# A214A.net
KiCad netlist of a schematic drawn in EAGLE
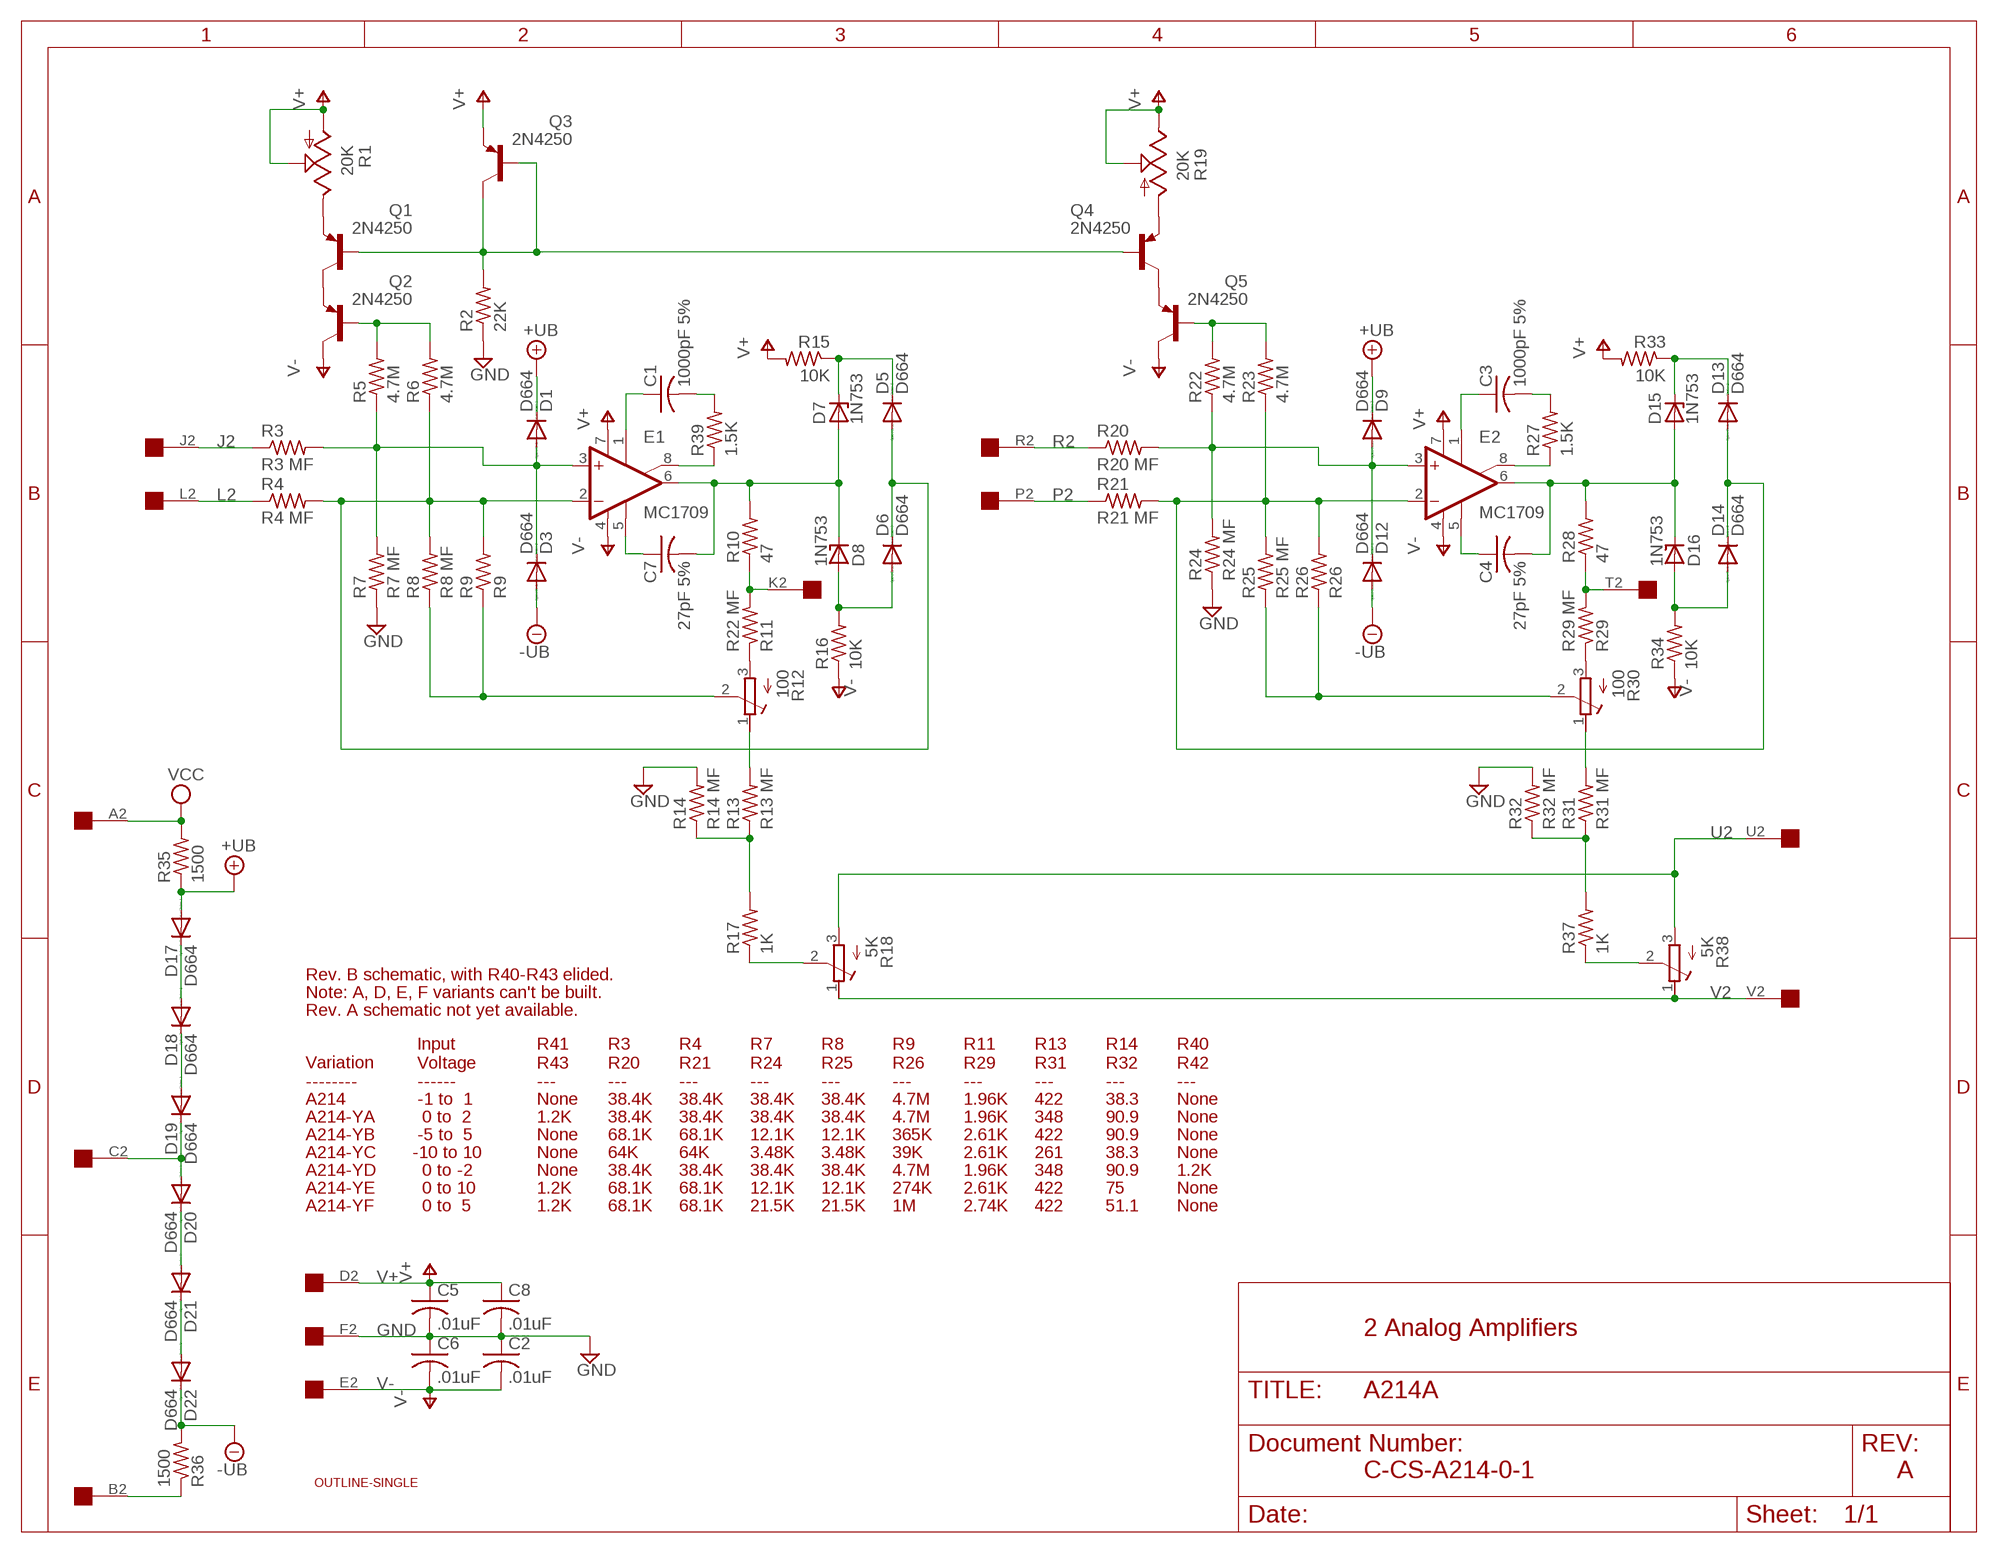
[diagram p0: schematic, sheet 1]

(export (version "E")
  (design (tool "Eeschema 10.0.6"))
  (components
    (comp (ref "C1")
      (value "1000pF 5%")
      (footprint "eagle-import:C050-030X075")
      (libsource (lib "eagle-import") (part "C-US050-030X075"))
    )
    (comp (ref "C2")
      (value ".01uF")
      (footprint "eagle-import:C063-025X075")
      (libsource (lib "eagle-import") (part "C-US"))
    )
    (comp (ref "C3")
      (value "1000pF 5%")
      (footprint "eagle-import:C050-030X075")
      (libsource (lib "eagle-import") (part "C-US050-030X075"))
    )
    (comp (ref "C4")
      (value "27pF 5%")
      (footprint "eagle-import:C063-025X075")
      (libsource (lib "eagle-import") (part "C-US"))
    )
    (comp (ref "C5")
      (value ".01uF")
      (footprint "eagle-import:C063-025X075")
      (libsource (lib "eagle-import") (part "C-US"))
    )
    (comp (ref "C6")
      (value ".01uF")
      (footprint "eagle-import:C063-025X075")
      (libsource (lib "eagle-import") (part "C-US"))
    )
    (comp (ref "C7")
      (value "27pF 5%")
      (footprint "eagle-import:C063-025X075")
      (libsource (lib "eagle-import") (part "C-US"))
    )
    (comp (ref "C8")
      (value ".01uF")
      (footprint "eagle-import:C063-025X075")
      (libsource (lib "eagle-import") (part "C-US"))
    )
    (comp (ref "D1")
      (value "D664")
      (footprint "eagle-import:DO35-10")
      (libsource (lib "eagle-import") (part "DIODE-DO35-10"))
    )
    (comp (ref "D3")
      (value "D664")
      (footprint "eagle-import:DO35-10")
      (libsource (lib "eagle-import") (part "DIODE-DO35-10"))
    )
    (comp (ref "D5")
      (value "D664")
      (footprint "eagle-import:DO35-10")
      (libsource (lib "eagle-import") (part "DIODE-DO35-10"))
    )
    (comp (ref "D6")
      (value "D664")
      (footprint "eagle-import:DO35-10")
      (libsource (lib "eagle-import") (part "DIODE-DO35-10"))
    )
    (comp (ref "D7")
      (value "1N753")
      (footprint "eagle-import:DO41Z10")
      (libsource (lib "eagle-import") (part "ZENER-DIODEDO41Z10"))
    )
    (comp (ref "D8")
      (value "1N753")
      (footprint "eagle-import:DO41Z10")
      (libsource (lib "eagle-import") (part "ZENER-DIODEDO41Z10"))
    )
    (comp (ref "D9")
      (value "D664")
      (footprint "eagle-import:DO35-10")
      (libsource (lib "eagle-import") (part "DIODE-DO35-10"))
    )
    (comp (ref "D12")
      (value "D664")
      (footprint "eagle-import:DO35-10")
      (libsource (lib "eagle-import") (part "DIODE-DO35-10"))
    )
    (comp (ref "D13")
      (value "D664")
      (footprint "eagle-import:DO35-10")
      (libsource (lib "eagle-import") (part "DIODE-DO35-10"))
    )
    (comp (ref "D14")
      (value "D664")
      (footprint "eagle-import:DO35-10")
      (libsource (lib "eagle-import") (part "DIODE-DO35-10"))
    )
    (comp (ref "D15")
      (value "1N753")
      (footprint "eagle-import:DO41Z10")
      (libsource (lib "eagle-import") (part "ZENER-DIODEDO41Z10"))
    )
    (comp (ref "D16")
      (value "1N753")
      (footprint "eagle-import:DO41Z10")
      (libsource (lib "eagle-import") (part "ZENER-DIODEDO41Z10"))
    )
    (comp (ref "D17")
      (value "D664")
      (footprint "eagle-import:DO35-10")
      (libsource (lib "eagle-import") (part "DIODE-DO35-10"))
    )
    (comp (ref "D18")
      (value "D664")
      (footprint "eagle-import:DO35-10")
      (libsource (lib "eagle-import") (part "DIODE-DO35-10"))
    )
    (comp (ref "D19")
      (value "D664")
      (footprint "eagle-import:DO35-10")
      (libsource (lib "eagle-import") (part "DIODE-DO35-10"))
    )
    (comp (ref "D20")
      (value "D664")
      (footprint "eagle-import:DO35-10")
      (libsource (lib "eagle-import") (part "DIODE-DO35-10"))
    )
    (comp (ref "D21")
      (value "D664")
      (footprint "eagle-import:DO35-10")
      (libsource (lib "eagle-import") (part "DIODE-DO35-10"))
    )
    (comp (ref "D22")
      (value "D664")
      (footprint "eagle-import:DO35-10")
      (libsource (lib "eagle-import") (part "DIODE-DO35-10"))
    )
    (comp (ref "E1")
      (value "MC1709")
      (footprint "eagle-import:H08C")
      (libsource (lib "eagle-import") (part "MC1709"))
    )
    (comp (ref "E2")
      (value "MC1709")
      (footprint "eagle-import:H08C")
      (libsource (lib "eagle-import") (part "MC1709"))
    )
    (comp (ref "Q1")
      (value "2N4250")
      (footprint "eagle-import:TO5")
      (libsource (lib "eagle-import") (part "-PNP-TO5"))
    )
    (comp (ref "Q2")
      (value "2N4250")
      (footprint "eagle-import:TO5")
      (libsource (lib "eagle-import") (part "-PNP-TO5"))
    )
    (comp (ref "Q3")
      (value "2N4250")
      (footprint "eagle-import:TO5")
      (libsource (lib "eagle-import") (part "-PNP-TO5"))
    )
    (comp (ref "Q4")
      (value "2N4250")
      (footprint "eagle-import:TO5")
      (libsource (lib "eagle-import") (part "-PNP-TO5"))
    )
    (comp (ref "Q5")
      (value "2N4250")
      (footprint "eagle-import:TO5")
      (libsource (lib "eagle-import") (part "-PNP-TO5"))
    )
    (comp (ref "R1")
      (value "20K")
      (footprint "eagle-import:B25P")
      (libsource (lib "eagle-import") (part "TRIM_US-B25P"))
    )
    (comp (ref "R2")
      (value "22K")
      (footprint "eagle-import:0207_10")
      (libsource (lib "eagle-import") (part "R-US_0207/10"))
    )
    (comp (ref "R3")
      (value "R3 MF")
      (footprint "eagle-import:0207_15")
      (libsource (lib "eagle-import") (part "R-US_0207/15"))
    )
    (comp (ref "R4")
      (value "R4 MF")
      (footprint "eagle-import:0207_15")
      (libsource (lib "eagle-import") (part "R-US_0207/15"))
    )
    (comp (ref "R5")
      (value "4.7M")
      (footprint "eagle-import:0207_10")
      (libsource (lib "eagle-import") (part "R-US_0207/10"))
    )
    (comp (ref "R6")
      (value "4.7M")
      (footprint "eagle-import:0207_10")
      (libsource (lib "eagle-import") (part "R-US_0207/10"))
    )
    (comp (ref "R7")
      (value "R7 MF")
      (footprint "eagle-import:0207_15")
      (libsource (lib "eagle-import") (part "R-US_0207/15"))
    )
    (comp (ref "R8")
      (value "R8 MF")
      (footprint "eagle-import:0207_15")
      (libsource (lib "eagle-import") (part "R-US_0207/15"))
    )
    (comp (ref "R9")
      (value "R9")
      (footprint "eagle-import:0207_10")
      (libsource (lib "eagle-import") (part "R-US_0207/10"))
    )
    (comp (ref "R10")
      (value "47")
      (footprint "eagle-import:0207_10")
      (libsource (lib "eagle-import") (part "R-US_0207/10"))
    )
    (comp (ref "R11")
      (value "R22 MF")
      (footprint "eagle-import:0207_15")
      (libsource (lib "eagle-import") (part "R-US_0207/15"))
    )
    (comp (ref "R12")
      (value "100")
      (footprint "eagle-import:3006Y")
      (libsource (lib "eagle-import") (part "275P"))
    )
    (comp (ref "R13")
      (value "R13 MF")
      (footprint "eagle-import:0207_15")
      (libsource (lib "eagle-import") (part "R-US_0207/15"))
    )
    (comp (ref "R14")
      (value "R14 MF")
      (footprint "eagle-import:0207_15")
      (libsource (lib "eagle-import") (part "R-US_0207/15"))
    )
    (comp (ref "R15")
      (value "10K")
      (footprint "eagle-import:0207_10")
      (libsource (lib "eagle-import") (part "R-US_0207/10"))
    )
    (comp (ref "R16")
      (value "10K")
      (footprint "eagle-import:0207_10")
      (libsource (lib "eagle-import") (part "R-US_0207/10"))
    )
    (comp (ref "R17")
      (value "1K")
      (footprint "eagle-import:0207_10")
      (libsource (lib "eagle-import") (part "R-US_0207/10"))
    )
    (comp (ref "R18")
      (value "5K")
      (footprint "eagle-import:3006Y")
      (libsource (lib "eagle-import") (part "275P"))
    )
    (comp (ref "R19")
      (value "20K")
      (footprint "eagle-import:B25P")
      (libsource (lib "eagle-import") (part "TRIM_US-B25P"))
    )
    (comp (ref "R20")
      (value "R20 MF")
      (footprint "eagle-import:0207_15")
      (libsource (lib "eagle-import") (part "R-US_0207/15"))
    )
    (comp (ref "R21")
      (value "R21 MF")
      (footprint "eagle-import:0207_15")
      (libsource (lib "eagle-import") (part "R-US_0207/15"))
    )
    (comp (ref "R22")
      (value "4.7M")
      (footprint "eagle-import:0207_10")
      (libsource (lib "eagle-import") (part "R-US_0207/10"))
    )
    (comp (ref "R23")
      (value "4.7M")
      (footprint "eagle-import:0207_10")
      (libsource (lib "eagle-import") (part "R-US_0207/10"))
    )
    (comp (ref "R24")
      (value "R24 MF")
      (footprint "eagle-import:0207_15")
      (libsource (lib "eagle-import") (part "R-US_0207/15"))
    )
    (comp (ref "R25")
      (value "R25 MF")
      (footprint "eagle-import:0207_15")
      (libsource (lib "eagle-import") (part "R-US_0207/15"))
    )
    (comp (ref "R26")
      (value "R26")
      (footprint "eagle-import:0207_10")
      (libsource (lib "eagle-import") (part "R-US_0207/10"))
    )
    (comp (ref "R27")
      (value "1.5K")
      (footprint "eagle-import:0207_10")
      (libsource (lib "eagle-import") (part "R-US_0207/10"))
    )
    (comp (ref "R28")
      (value "47")
      (footprint "eagle-import:0207_10")
      (libsource (lib "eagle-import") (part "R-US_0207/10"))
    )
    (comp (ref "R29")
      (value "R29 MF")
      (footprint "eagle-import:0207_15")
      (libsource (lib "eagle-import") (part "R-US_0207/15"))
    )
    (comp (ref "R30")
      (value "100")
      (footprint "eagle-import:3006Y")
      (libsource (lib "eagle-import") (part "275P"))
    )
    (comp (ref "R31")
      (value "R31 MF")
      (footprint "eagle-import:0207_15")
      (libsource (lib "eagle-import") (part "R-US_0207/15"))
    )
    (comp (ref "R32")
      (value "R32 MF")
      (footprint "eagle-import:0207_15")
      (libsource (lib "eagle-import") (part "R-US_0207/15"))
    )
    (comp (ref "R33")
      (value "10K")
      (footprint "eagle-import:0207_10")
      (libsource (lib "eagle-import") (part "R-US_0207/10"))
    )
    (comp (ref "R34")
      (value "10K")
      (footprint "eagle-import:0207_10")
      (libsource (lib "eagle-import") (part "R-US_0207/10"))
    )
    (comp (ref "R35")
      (value "1500")
      (footprint "eagle-import:0207_10")
      (libsource (lib "eagle-import") (part "R-US_0207/10"))
    )
    (comp (ref "R36")
      (value "1500")
      (footprint "eagle-import:0207_10")
      (libsource (lib "eagle-import") (part "R-US_0207/10"))
    )
    (comp (ref "R37")
      (value "1K")
      (footprint "eagle-import:0207_10")
      (libsource (lib "eagle-import") (part "R-US_0207/10"))
    )
    (comp (ref "R38")
      (value "5K")
      (footprint "eagle-import:3006Y")
      (libsource (lib "eagle-import") (part "275P"))
    )
    (comp (ref "R39")
      (value "1.5K")
      (footprint "eagle-import:0207_10")
      (libsource (lib "eagle-import") (part "R-US_0207/10"))
    )
    (comp (ref "U$1")
      (value "OUTLINE-SINGLE")
      (footprint "eagle-import:SINGLE")
      (libsource (lib "eagle-import") (part "OUTLINE-SINGLE"))
    )
    (comp (ref "U$2")
      (value "SINGLE")
      (footprint "eagle-import:EDGE-CON2")
      (libsource (lib "eagle-import") (part "SINGLE"))
    )
  )
  (nets
    (net (code "1") (name "+UB") (class "Default")
      (node (ref "D1") (pin "C") (pinfunction "C_C") (pintype "passive"))
      (node (ref "D17") (pin "A") (pinfunction "A_A") (pintype "passive"))
      (node (ref "D9") (pin "C") (pinfunction "C_C") (pintype "passive"))
      (node (ref "R35") (pin "1") (pinfunction "1_1") (pintype "passive"))
    )
    (net (code "2") (name "-UB") (class "Default")
      (node (ref "D12") (pin "A") (pinfunction "A_A") (pintype "passive"))
      (node (ref "D22") (pin "C") (pinfunction "C_C") (pintype "passive"))
      (node (ref "D3") (pin "A") (pinfunction "A_A") (pintype "passive"))
      (node (ref "R36") (pin "2") (pinfunction "2_2") (pintype "passive"))
    )
    (net (code "3") (name "/J2") (class "Default")
      (node (ref "R3") (pin "1") (pinfunction "1_1") (pintype "passive"))
      (node (ref "U$2") (pin "J2") (pinfunction "1_J2") (pintype "bidirectional"))
    )
    (net (code "4") (name "/L2") (class "Default")
      (node (ref "R4") (pin "1") (pinfunction "1_1") (pintype "passive"))
      (node (ref "U$2") (pin "L2") (pinfunction "1_L2") (pintype "bidirectional"))
    )
    (net (code "5") (name "/P2") (class "Default")
      (node (ref "R21") (pin "1") (pinfunction "1_1") (pintype "passive"))
      (node (ref "U$2") (pin "P2") (pinfunction "1_P2") (pintype "bidirectional"))
    )
    (net (code "6") (name "/R2") (class "Default")
      (node (ref "R20") (pin "1") (pinfunction "1_1") (pintype "passive"))
      (node (ref "U$2") (pin "R2") (pinfunction "1_R2") (pintype "bidirectional"))
    )
    (net (code "7") (name "/U2") (class "Default")
      (node (ref "R18") (pin "3") (pinfunction "E_3") (pintype "passive"))
      (node (ref "R38") (pin "3") (pinfunction "E_3") (pintype "passive"))
      (node (ref "U$2") (pin "U2") (pinfunction "1_U2") (pintype "bidirectional"))
    )
    (net (code "8") (name "/V2") (class "Default")
      (node (ref "R18") (pin "1") (pinfunction "A_1") (pintype "passive"))
      (node (ref "R38") (pin "1") (pinfunction "A_1") (pintype "passive"))
      (node (ref "U$2") (pin "V2") (pinfunction "1_V2") (pintype "bidirectional"))
    )
    (net (code "9") (name "GND") (class "Default")
      (node (ref "C2") (pin "1") (pinfunction "1_1") (pintype "passive"))
      (node (ref "C5") (pin "2") (pinfunction "2_2") (pintype "passive"))
      (node (ref "C6") (pin "1") (pinfunction "1_1") (pintype "passive"))
      (node (ref "C8") (pin "2") (pinfunction "2_2") (pintype "passive"))
      (node (ref "R14") (pin "2") (pinfunction "2_2") (pintype "passive"))
      (node (ref "R2") (pin "1") (pinfunction "1_1") (pintype "passive"))
      (node (ref "R24") (pin "1") (pinfunction "1_1") (pintype "passive"))
      (node (ref "R32") (pin "2") (pinfunction "2_2") (pintype "passive"))
      (node (ref "R7") (pin "1") (pinfunction "1_1") (pintype "passive"))
      (node (ref "U$2") (pin "F2") (pinfunction "1_F2") (pintype "bidirectional"))
    )
    (net (code "10") (name "Net-(C1-Pad2)") (class "Default")
      (node (ref "C1") (pin "2") (pinfunction "2_2") (pintype "passive"))
      (node (ref "R39") (pin "2") (pinfunction "2_2") (pintype "passive"))
    )
    (net (code "11") (name "Net-(C3-Pad2)") (class "Default")
      (node (ref "C3") (pin "2") (pinfunction "2_2") (pintype "passive"))
      (node (ref "R27") (pin "2") (pinfunction "2_2") (pintype "passive"))
    )
    (net (code "12") (name "Net-(D5-PadC)") (class "Default")
      (node (ref "D5") (pin "C") (pinfunction "C_C") (pintype "passive"))
      (node (ref "D7") (pin "C") (pinfunction "C_C") (pintype "passive"))
      (node (ref "R15") (pin "1") (pinfunction "1_1") (pintype "passive"))
    )
    (net (code "13") (name "Net-(D6-PadA)") (class "Default")
      (node (ref "D6") (pin "A") (pinfunction "A_A") (pintype "passive"))
      (node (ref "D8") (pin "A") (pinfunction "A_A") (pintype "passive"))
      (node (ref "R16") (pin "2") (pinfunction "2_2") (pintype "passive"))
    )
    (net (code "14") (name "Net-(D13-PadC)") (class "Default")
      (node (ref "D13") (pin "C") (pinfunction "C_C") (pintype "passive"))
      (node (ref "D15") (pin "C") (pinfunction "C_C") (pintype "passive"))
      (node (ref "R33") (pin "1") (pinfunction "1_1") (pintype "passive"))
    )
    (net (code "15") (name "Net-(D14-PadA)") (class "Default")
      (node (ref "D14") (pin "A") (pinfunction "A_A") (pintype "passive"))
      (node (ref "D16") (pin "A") (pinfunction "A_A") (pintype "passive"))
      (node (ref "R34") (pin "2") (pinfunction "2_2") (pintype "passive"))
    )
    (net (code "16") (name "Net-(D17-PadC)") (class "Default")
      (node (ref "D17") (pin "C") (pinfunction "C_C") (pintype "passive"))
      (node (ref "D18") (pin "A") (pinfunction "A_A") (pintype "passive"))
    )
    (net (code "17") (name "Net-(D18-PadC)") (class "Default")
      (node (ref "D18") (pin "C") (pinfunction "C_C") (pintype "passive"))
      (node (ref "D19") (pin "A") (pinfunction "A_A") (pintype "passive"))
    )
    (net (code "18") (name "Net-(D20-PadC)") (class "Default")
      (node (ref "D20") (pin "C") (pinfunction "C_C") (pintype "passive"))
      (node (ref "D21") (pin "A") (pinfunction "A_A") (pintype "passive"))
    )
    (net (code "19") (name "Net-(D21-PadC)") (class "Default")
      (node (ref "D21") (pin "C") (pinfunction "C_C") (pintype "passive"))
      (node (ref "D22") (pin "A") (pinfunction "A_A") (pintype "passive"))
    )
    (net (code "20") (name "Net-(E1-+IN)") (class "Default")
      (node (ref "D1") (pin "A") (pinfunction "A_A") (pintype "passive"))
      (node (ref "D3") (pin "C") (pinfunction "C_C") (pintype "passive"))
      (node (ref "E1") (pin "3") (pinfunction "+IN_3") (pintype "input"))
      (node (ref "R3") (pin "2") (pinfunction "2_2") (pintype "passive"))
      (node (ref "R5") (pin "1") (pinfunction "1_1") (pintype "passive"))
      (node (ref "R7") (pin "2") (pinfunction "2_2") (pintype "passive"))
    )
    (net (code "21") (name "Net-(E1--IN)") (class "Default")
      (node (ref "D5") (pin "A") (pinfunction "A_A") (pintype "passive"))
      (node (ref "D6") (pin "C") (pinfunction "C_C") (pintype "passive"))
      (node (ref "E1") (pin "2") (pinfunction "-IN_2") (pintype "input"))
      (node (ref "R4") (pin "2") (pinfunction "2_2") (pintype "passive"))
      (node (ref "R6") (pin "1") (pinfunction "1_1") (pintype "passive"))
      (node (ref "R8") (pin "2") (pinfunction "2_2") (pintype "passive"))
      (node (ref "R9") (pin "2") (pinfunction "2_2") (pintype "passive"))
    )
    (net (code "22") (name "Net-(E1-ON1)") (class "Default")
      (node (ref "C1") (pin "1") (pinfunction "1_1") (pintype "passive"))
      (node (ref "E1") (pin "1") (pinfunction "ON1_1") (pintype "passive"))
    )
    (net (code "23") (name "Net-(E1-ON2)") (class "Default")
      (node (ref "E1") (pin "8") (pinfunction "ON2_8") (pintype "passive"))
      (node (ref "R39") (pin "1") (pinfunction "1_1") (pintype "passive"))
    )
    (net (code "24") (name "Net-(E1-OPT)") (class "Default")
      (node (ref "C7") (pin "1") (pinfunction "1_1") (pintype "passive"))
      (node (ref "E1") (pin "5") (pinfunction "OPT_5") (pintype "passive"))
    )
    (net (code "25") (name "Net-(E1-OUT)") (class "Default")
      (node (ref "C7") (pin "2") (pinfunction "2_2") (pintype "passive"))
      (node (ref "D7") (pin "A") (pinfunction "A_A") (pintype "passive"))
      (node (ref "D8") (pin "C") (pinfunction "C_C") (pintype "passive"))
      (node (ref "E1") (pin "6") (pinfunction "OUT_6") (pintype "output"))
      (node (ref "R10") (pin "2") (pinfunction "2_2") (pintype "passive"))
    )
    (net (code "26") (name "Net-(E2-+IN)") (class "Default")
      (node (ref "D12") (pin "C") (pinfunction "C_C") (pintype "passive"))
      (node (ref "D9") (pin "A") (pinfunction "A_A") (pintype "passive"))
      (node (ref "E2") (pin "3") (pinfunction "+IN_3") (pintype "input"))
      (node (ref "R20") (pin "2") (pinfunction "2_2") (pintype "passive"))
      (node (ref "R22") (pin "1") (pinfunction "1_1") (pintype "passive"))
      (node (ref "R24") (pin "2") (pinfunction "2_2") (pintype "passive"))
    )
    (net (code "27") (name "Net-(E2--IN)") (class "Default")
      (node (ref "D13") (pin "A") (pinfunction "A_A") (pintype "passive"))
      (node (ref "D14") (pin "C") (pinfunction "C_C") (pintype "passive"))
      (node (ref "E2") (pin "2") (pinfunction "-IN_2") (pintype "input"))
      (node (ref "R21") (pin "2") (pinfunction "2_2") (pintype "passive"))
      (node (ref "R23") (pin "1") (pinfunction "1_1") (pintype "passive"))
      (node (ref "R25") (pin "2") (pinfunction "2_2") (pintype "passive"))
      (node (ref "R26") (pin "2") (pinfunction "2_2") (pintype "passive"))
    )
    (net (code "28") (name "Net-(E2-ON1)") (class "Default")
      (node (ref "C3") (pin "1") (pinfunction "1_1") (pintype "passive"))
      (node (ref "E2") (pin "1") (pinfunction "ON1_1") (pintype "passive"))
    )
    (net (code "29") (name "Net-(E2-ON2)") (class "Default")
      (node (ref "E2") (pin "8") (pinfunction "ON2_8") (pintype "passive"))
      (node (ref "R27") (pin "1") (pinfunction "1_1") (pintype "passive"))
    )
    (net (code "30") (name "Net-(E2-OPT)") (class "Default")
      (node (ref "C4") (pin "1") (pinfunction "1_1") (pintype "passive"))
      (node (ref "E2") (pin "5") (pinfunction "OPT_5") (pintype "passive"))
    )
    (net (code "31") (name "Net-(E2-OUT)") (class "Default")
      (node (ref "C4") (pin "2") (pinfunction "2_2") (pintype "passive"))
      (node (ref "D15") (pin "A") (pinfunction "A_A") (pintype "passive"))
      (node (ref "D16") (pin "C") (pinfunction "C_C") (pintype "passive"))
      (node (ref "E2") (pin "6") (pinfunction "OUT_6") (pintype "output"))
      (node (ref "R28") (pin "2") (pinfunction "2_2") (pintype "passive"))
    )
    (net (code "32") (name "Net-(Q1-B)") (class "Default")
      (node (ref "Q1") (pin "2") (pinfunction "B_2") (pintype "passive"))
      (node (ref "Q3") (pin "2") (pinfunction "B_2") (pintype "passive"))
      (node (ref "Q3") (pin "3") (pinfunction "C_3") (pintype "passive"))
      (node (ref "Q4") (pin "2") (pinfunction "B_2") (pintype "passive"))
      (node (ref "R2") (pin "2") (pinfunction "2_2") (pintype "passive"))
    )
    (net (code "33") (name "Net-(Q1-C)") (class "Default")
      (node (ref "Q1") (pin "3") (pinfunction "C_3") (pintype "passive"))
      (node (ref "Q2") (pin "1") (pinfunction "E_1") (pintype "passive"))
    )
    (net (code "34") (name "Net-(Q1-E)") (class "Default")
      (node (ref "Q1") (pin "1") (pinfunction "E_1") (pintype "passive"))
      (node (ref "R1") (pin "E") (pinfunction "E_E") (pintype "passive"))
    )
    (net (code "35") (name "Net-(Q2-B)") (class "Default")
      (node (ref "Q2") (pin "2") (pinfunction "B_2") (pintype "passive"))
      (node (ref "R5") (pin "2") (pinfunction "2_2") (pintype "passive"))
      (node (ref "R6") (pin "2") (pinfunction "2_2") (pintype "passive"))
    )
    (net (code "36") (name "Net-(Q4-C)") (class "Default")
      (node (ref "Q4") (pin "3") (pinfunction "C_3") (pintype "passive"))
      (node (ref "Q5") (pin "1") (pinfunction "E_1") (pintype "passive"))
    )
    (net (code "37") (name "Net-(Q4-E)") (class "Default")
      (node (ref "Q4") (pin "1") (pinfunction "E_1") (pintype "passive"))
      (node (ref "R19") (pin "A") (pinfunction "A_A") (pintype "passive"))
    )
    (net (code "38") (name "Net-(Q5-B)") (class "Default")
      (node (ref "Q5") (pin "2") (pinfunction "B_2") (pintype "passive"))
      (node (ref "R22") (pin "2") (pinfunction "2_2") (pintype "passive"))
      (node (ref "R23") (pin "2") (pinfunction "2_2") (pintype "passive"))
    )
    (net (code "39") (name "Net-(R12-A)") (class "Default")
      (node (ref "R12") (pin "1") (pinfunction "A_1") (pintype "passive"))
      (node (ref "R13") (pin "2") (pinfunction "2_2") (pintype "passive"))
    )
    (net (code "40") (name "Net-(R12-E)") (class "Default")
      (node (ref "R11") (pin "1") (pinfunction "1_1") (pintype "passive"))
      (node (ref "R12") (pin "3") (pinfunction "E_3") (pintype "passive"))
    )
    (net (code "41") (name "Net-(R12-S)") (class "Default")
      (node (ref "R12") (pin "2") (pinfunction "S_2") (pintype "passive"))
      (node (ref "R8") (pin "1") (pinfunction "1_1") (pintype "passive"))
      (node (ref "R9") (pin "1") (pinfunction "1_1") (pintype "passive"))
    )
    (net (code "42") (name "Net-(R13-Pad1)") (class "Default")
      (node (ref "R13") (pin "1") (pinfunction "1_1") (pintype "passive"))
      (node (ref "R14") (pin "1") (pinfunction "1_1") (pintype "passive"))
      (node (ref "R17") (pin "2") (pinfunction "2_2") (pintype "passive"))
    )
    (net (code "43") (name "Net-(R18-S)") (class "Default")
      (node (ref "R17") (pin "1") (pinfunction "1_1") (pintype "passive"))
      (node (ref "R18") (pin "2") (pinfunction "S_2") (pintype "passive"))
    )
    (net (code "44") (name "Net-(R30-A)") (class "Default")
      (node (ref "R30") (pin "1") (pinfunction "A_1") (pintype "passive"))
      (node (ref "R31") (pin "2") (pinfunction "2_2") (pintype "passive"))
    )
    (net (code "45") (name "Net-(R30-E)") (class "Default")
      (node (ref "R29") (pin "1") (pinfunction "1_1") (pintype "passive"))
      (node (ref "R30") (pin "3") (pinfunction "E_3") (pintype "passive"))
    )
    (net (code "46") (name "Net-(R30-S)") (class "Default")
      (node (ref "R25") (pin "1") (pinfunction "1_1") (pintype "passive"))
      (node (ref "R26") (pin "1") (pinfunction "1_1") (pintype "passive"))
      (node (ref "R30") (pin "2") (pinfunction "S_2") (pintype "passive"))
    )
    (net (code "47") (name "Net-(R31-Pad1)") (class "Default")
      (node (ref "R31") (pin "1") (pinfunction "1_1") (pintype "passive"))
      (node (ref "R32") (pin "1") (pinfunction "1_1") (pintype "passive"))
      (node (ref "R37") (pin "2") (pinfunction "2_2") (pintype "passive"))
    )
    (net (code "48") (name "Net-(R38-S)") (class "Default")
      (node (ref "R37") (pin "1") (pinfunction "1_1") (pintype "passive"))
      (node (ref "R38") (pin "2") (pinfunction "S_2") (pintype "passive"))
    )
    (net (code "49") (name "Net-(U$2AF-1)") (class "Default")
      (node (ref "R28") (pin "1") (pinfunction "1_1") (pintype "passive"))
      (node (ref "R29") (pin "2") (pinfunction "2_2") (pintype "passive"))
      (node (ref "U$2") (pin "T2") (pinfunction "1_T2") (pintype "bidirectional"))
    )
    (net (code "50") (name "Net-(U$2D-1)") (class "Default")
      (node (ref "R36") (pin "1") (pinfunction "1_1") (pintype "passive"))
      (node (ref "U$2") (pin "B2") (pinfunction "1_B2") (pintype "bidirectional"))
    )
    (net (code "51") (name "Net-(U$2F-1)") (class "Default")
      (node (ref "D19") (pin "C") (pinfunction "C_C") (pintype "passive"))
      (node (ref "D20") (pin "A") (pinfunction "A_A") (pintype "passive"))
      (node (ref "U$2") (pin "C2") (pinfunction "1_C2") (pintype "bidirectional"))
    )
    (net (code "52") (name "Net-(U$2R-1)") (class "Default")
      (node (ref "R10") (pin "1") (pinfunction "1_1") (pintype "passive"))
      (node (ref "R11") (pin "2") (pinfunction "2_2") (pintype "passive"))
      (node (ref "U$2") (pin "K2") (pinfunction "1_K2") (pintype "bidirectional"))
    )
    (net (code "53") (name "V+") (class "Default")
      (node (ref "C5") (pin "1") (pinfunction "1_1") (pintype "passive"))
      (node (ref "C8") (pin "1") (pinfunction "1_1") (pintype "passive"))
      (node (ref "E1") (pin "7") (pinfunction "V+_7") (pintype "power_in"))
      (node (ref "E2") (pin "7") (pinfunction "V+_7") (pintype "power_in"))
      (node (ref "Q3") (pin "1") (pinfunction "E_1") (pintype "passive"))
      (node (ref "R1") (pin "A") (pinfunction "A_A") (pintype "passive"))
      (node (ref "R1") (pin "S") (pinfunction "S_S") (pintype "passive"))
      (node (ref "R15") (pin "2") (pinfunction "2_2") (pintype "passive"))
      (node (ref "R19") (pin "E") (pinfunction "E_E") (pintype "passive"))
      (node (ref "R19") (pin "S") (pinfunction "S_S") (pintype "passive"))
      (node (ref "R33") (pin "2") (pinfunction "2_2") (pintype "passive"))
      (node (ref "U$2") (pin "D2") (pinfunction "1_D2") (pintype "bidirectional"))
    )
    (net (code "54") (name "V-") (class "Default")
      (node (ref "C2") (pin "2") (pinfunction "2_2") (pintype "passive"))
      (node (ref "C6") (pin "2") (pinfunction "2_2") (pintype "passive"))
      (node (ref "E1") (pin "4") (pinfunction "V-_4") (pintype "power_in"))
      (node (ref "E2") (pin "4") (pinfunction "V-_4") (pintype "power_in"))
      (node (ref "Q2") (pin "3") (pinfunction "C_3") (pintype "passive"))
      (node (ref "Q5") (pin "3") (pinfunction "C_3") (pintype "passive"))
      (node (ref "R16") (pin "1") (pinfunction "1_1") (pintype "passive"))
      (node (ref "R34") (pin "1") (pinfunction "1_1") (pintype "passive"))
      (node (ref "U$2") (pin "E2") (pinfunction "1_E2") (pintype "bidirectional"))
    )
    (net (code "55") (name "VCC") (class "Default")
      (node (ref "R35") (pin "2") (pinfunction "2_2") (pintype "passive"))
      (node (ref "U$2") (pin "A2") (pinfunction "1_A2") (pintype "bidirectional"))
    )
  )
)
